# Archer.net
KiCad netlist of a schematic drawn in EAGLE
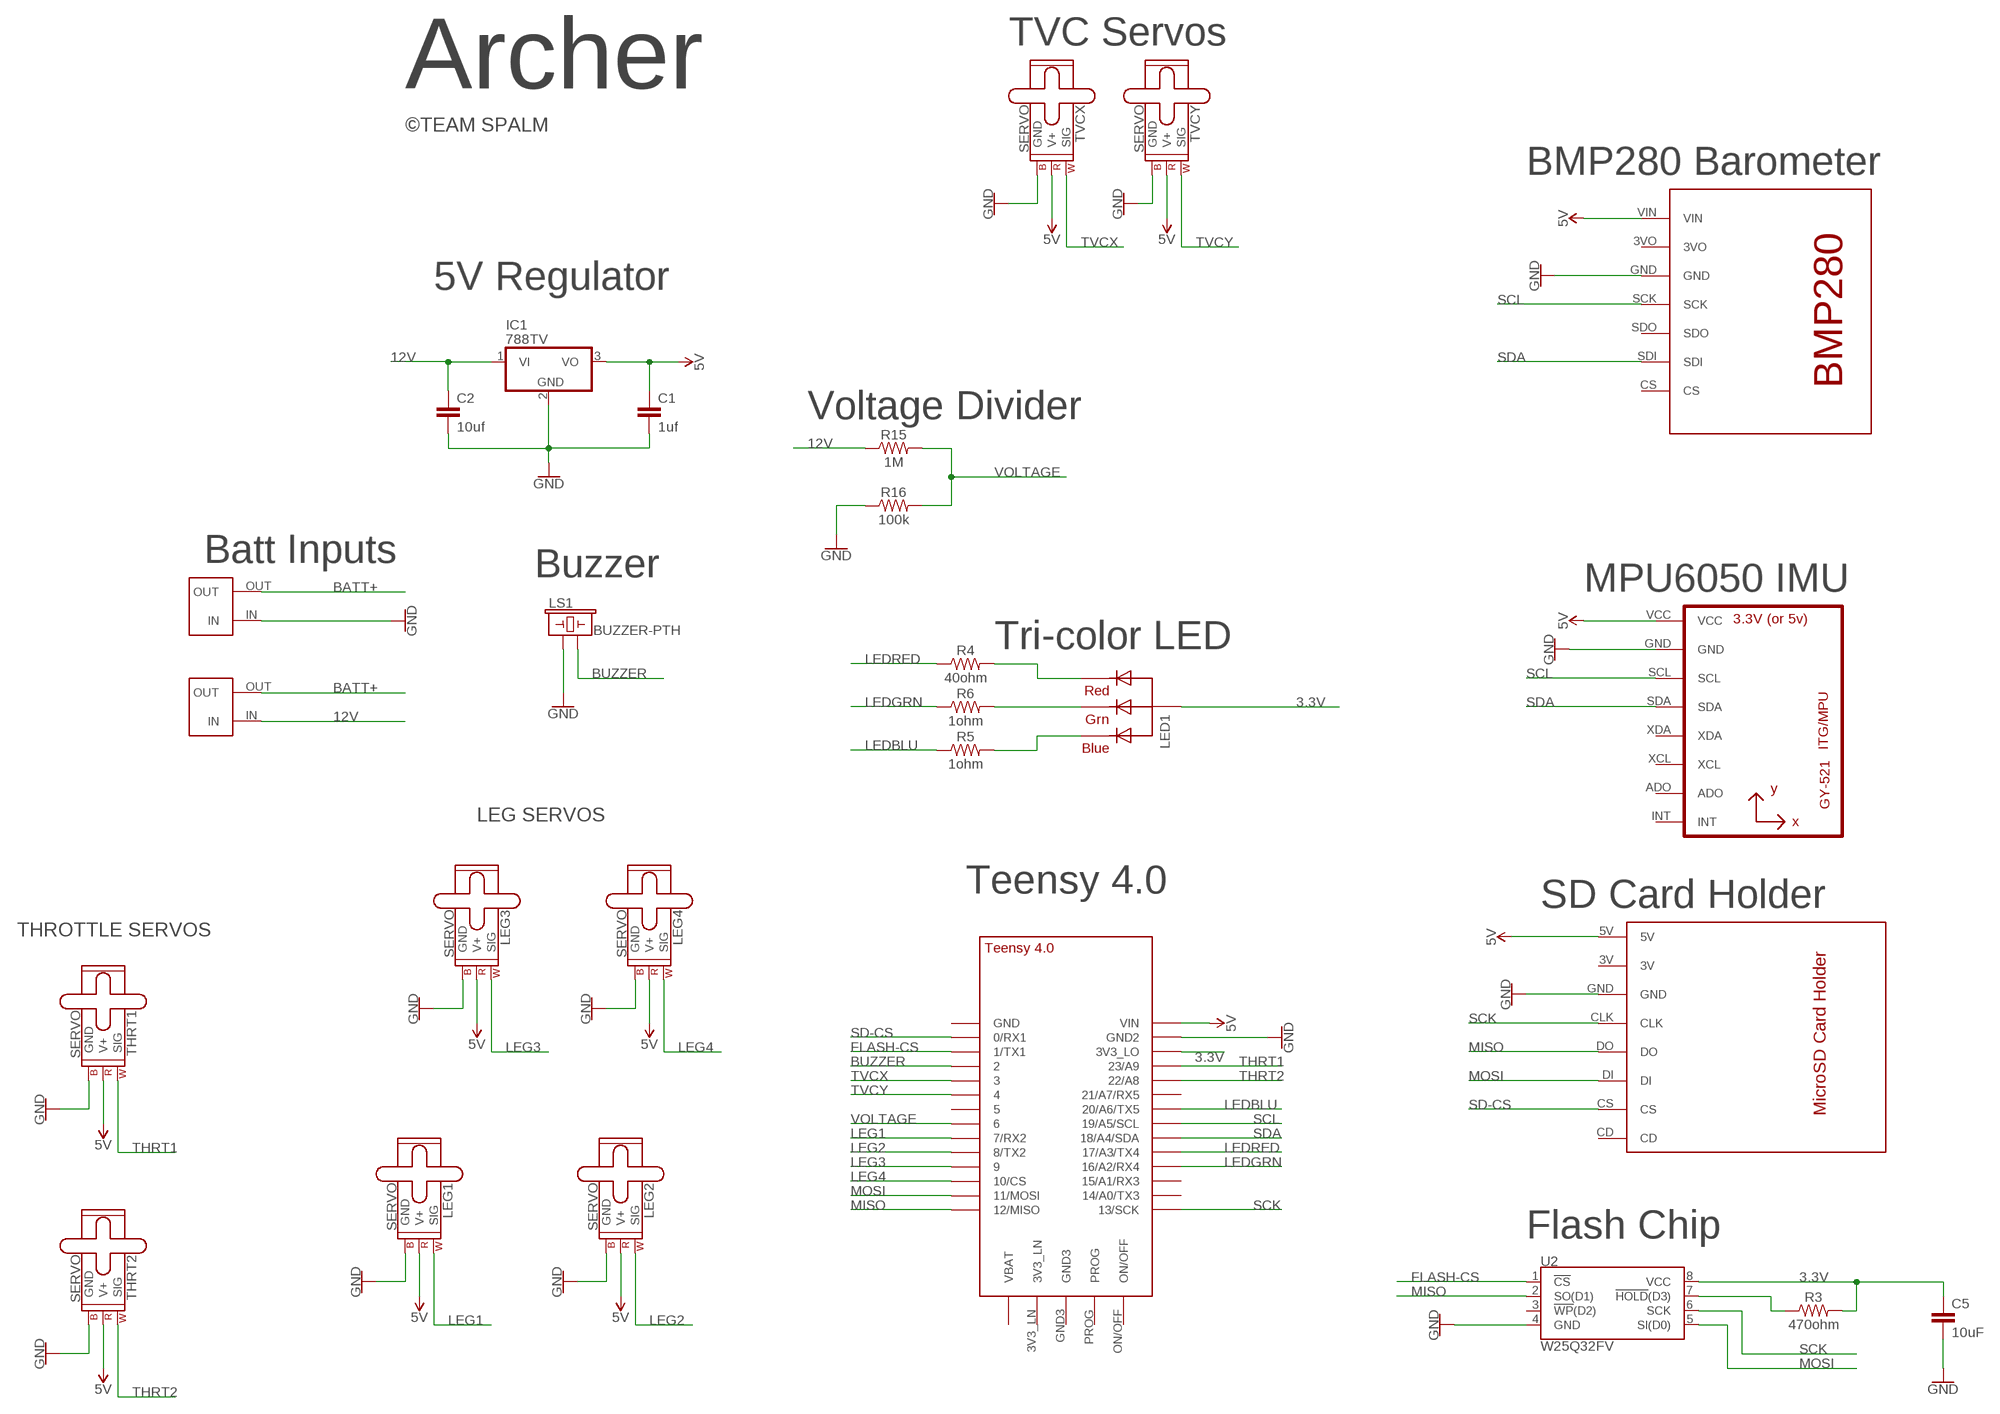
[diagram p0: schematic, sheet 1]

(export (version "E")
  (design (tool "Eeschema 10.0.6"))
  (components
    (comp (ref "C1")
      (value "1uf")
      (footprint "eagle-import:CAP-PTH-2.54")
      (libsource (lib "eagle-import") (part "22PF-PTH-2.54MM-200V-5%"))
    )
    (comp (ref "C2")
      (value "10uf")
      (footprint "eagle-import:CAP-PTH-2.54")
      (libsource (lib "eagle-import") (part "22PF-PTH-2.54MM-200V-5%"))
    )
    (comp (ref "C5")
      (value "10uF")
      (footprint "eagle-import:CAP-PTH-2.54")
      (libsource (lib "eagle-import") (part "22PF-PTH-2.54MM-200V-5%"))
    )
    (comp (ref "IC1")
      (value "788TV")
      (footprint "eagle-import:TO220V")
      (libsource (lib "eagle-import") (part "78TV8"))
    )
    (comp (ref "LED1")
      (value "RGBLED_CA-5MM")
      (footprint "eagle-import:LED5MMRGB")
      (libsource (lib "eagle-import") (part "RGBLED_CA-5MM"))
    )
    (comp (ref "LEG1")
      (value "SERVO")
      (footprint "eagle-import:1X03")
      (libsource (lib "eagle-import") (part "SERVO"))
    )
    (comp (ref "LEG2")
      (value "SERVO")
      (footprint "eagle-import:1X03")
      (libsource (lib "eagle-import") (part "SERVO"))
    )
    (comp (ref "LEG3")
      (value "SERVO")
      (footprint "eagle-import:1X03")
      (libsource (lib "eagle-import") (part "SERVO"))
    )
    (comp (ref "LEG4")
      (value "SERVO")
      (footprint "eagle-import:1X03")
      (libsource (lib "eagle-import") (part "SERVO"))
    )
    (comp (ref "LS1")
      (value "BUZZER-PTH")
      (footprint "eagle-import:BUZZER-12MM")
      (libsource (lib "eagle-import") (part "BUZZER-PTH"))
    )
    (comp (ref "R3")
      (value "470ohm")
      (footprint "eagle-import:AXIAL-0.3")
      (libsource (lib "eagle-import") (part "10MOHM-HORIZ-1/4W-5%"))
    )
    (comp (ref "R4")
      (value "40ohm")
      (footprint "eagle-import:AXIAL-0.3")
      (libsource (lib "eagle-import") (part "10MOHM-HORIZ-1/4W-5%"))
    )
    (comp (ref "R5")
      (value "1ohm")
      (footprint "eagle-import:AXIAL-0.3")
      (libsource (lib "eagle-import") (part "10MOHM-HORIZ-1/4W-5%"))
    )
    (comp (ref "R6")
      (value "1ohm")
      (footprint "eagle-import:AXIAL-0.3")
      (libsource (lib "eagle-import") (part "10MOHM-HORIZ-1/4W-5%"))
    )
    (comp (ref "R15")
      (value "1M")
      (footprint "eagle-import:AXIAL-0.3")
      (libsource (lib "eagle-import") (part "10MOHM-HORIZ-1/4W-5%"))
    )
    (comp (ref "R16")
      (value "100k")
      (footprint "eagle-import:AXIAL-0.3")
      (libsource (lib "eagle-import") (part "10MOHM-HORIZ-1/4W-5%"))
    )
    (comp (ref "TEENSY_4.0")
      (value "TEENSY_4.0")
      (footprint "eagle-import:TEENSY_4.0")
      (libsource (lib "eagle-import") (part "TEENSY_4.0"))
    )
    (comp (ref "THRT1")
      (value "SERVO")
      (footprint "eagle-import:1X03")
      (libsource (lib "eagle-import") (part "SERVO"))
    )
    (comp (ref "THRT2")
      (value "SERVO")
      (footprint "eagle-import:1X03")
      (libsource (lib "eagle-import") (part "SERVO"))
    )
    (comp (ref "TVCX")
      (value "SERVO")
      (footprint "eagle-import:1X03")
      (libsource (lib "eagle-import") (part "SERVO"))
    )
    (comp (ref "TVCY")
      (value "SERVO")
      (footprint "eagle-import:1X03")
      (libsource (lib "eagle-import") (part "SERVO"))
    )
    (comp (ref "U$2")
      (value "BMP280")
      (footprint "eagle-import:BMP280")
      (libsource (lib "eagle-import") (part "BMP280"))
    )
    (comp (ref "U$3")
      (value "MICROSDCARDHOLDER")
      (footprint "eagle-import:SDCARDHOLDER")
      (libsource (lib "eagle-import") (part "MICROSDCARDHOLDER"))
    )
    (comp (ref "U$8")
      (value "BLACKTERMBLOCK")
      (footprint "eagle-import:BLACKTERMBLOCK")
      (libsource (lib "eagle-import") (part "BLACKTERMBLOCK"))
    )
    (comp (ref "U$9")
      (value "BLACKTERMBLOCK")
      (footprint "eagle-import:BLACKTERMBLOCK")
      (libsource (lib "eagle-import") (part "BLACKTERMBLOCK"))
    )
    (comp (ref "U1")
      (value "GY-521MPU6050")
      (footprint "eagle-import:GY-521")
      (libsource (lib "eagle-import") (part "GY-521MPU6050"))
    )
    (comp (ref "U2")
      (value "W25Q32FV")
      (footprint "eagle-import:SOIC-8")
      (libsource (lib "eagle-import") (part "W25Q32FVSS"))
    )
  )
  (nets
    (net (code "1") (name "/3.3V") (class "Default")
      (node (ref "C5") (pin "1") (pinfunction "1_1") (pintype "passive"))
      (node (ref "LED1") (pin "2") (pinfunction "VCC_2") (pintype "bidirectional"))
      (node (ref "R3") (pin "P$2") (pinfunction "2_P$2") (pintype "passive"))
      (node (ref "TEENSY_4.0") (pin "3V3_LO") (pinfunction "3V3_LO_3V3_LO") (pintype "bidirectional"))
      (node (ref "U2") (pin "8") (pinfunction "VCC_8") (pintype "bidirectional"))
    )
    (net (code "2") (name "/12V") (class "Default")
      (node (ref "C2") (pin "1") (pinfunction "1_1") (pintype "passive"))
      (node (ref "IC1") (pin "1") (pinfunction "VI_1") (pintype "input"))
      (node (ref "R15") (pin "P$1") (pinfunction "1_P$1") (pintype "passive"))
      (node (ref "U$9") (pin "IN") (pinfunction "IN_IN") (pintype "bidirectional"))
    )
    (net (code "3") (name "/BATT+") (class "Default")
      (node (ref "U$8") (pin "OUT") (pinfunction "OUT_OUT") (pintype "bidirectional"))
      (node (ref "U$9") (pin "OUT") (pinfunction "OUT_OUT") (pintype "bidirectional"))
    )
    (net (code "4") (name "/BUZZER") (class "Default")
      (node (ref "LS1") (pin "-") (pinfunction "2_-") (pintype "passive"))
      (node (ref "TEENSY_4.0") (pin "2") (pinfunction "2_2") (pintype "bidirectional"))
    )
    (net (code "5") (name "/FLASH-CS") (class "Default")
      (node (ref "TEENSY_4.0") (pin "1/TX") (pinfunction "1/TX1_1/TX") (pintype "bidirectional"))
      (node (ref "U2") (pin "1") (pinfunction "~{CS}_1") (pintype "bidirectional"))
    )
    (net (code "6") (name "/LEDBLU") (class "Default")
      (node (ref "R5") (pin "P$1") (pinfunction "1_P$1") (pintype "passive"))
      (node (ref "TEENSY_4.0") (pin "20/A6") (pinfunction "20/A6/TX5_20/A6") (pintype "bidirectional"))
    )
    (net (code "7") (name "/LEDGRN") (class "Default")
      (node (ref "R6") (pin "P$1") (pinfunction "1_P$1") (pintype "passive"))
      (node (ref "TEENSY_4.0") (pin "16/A2") (pinfunction "16/A2/RX4_16/A2") (pintype "bidirectional"))
    )
    (net (code "8") (name "/LEDRED") (class "Default")
      (node (ref "R4") (pin "P$1") (pinfunction "1_P$1") (pintype "passive"))
      (node (ref "TEENSY_4.0") (pin "17/A3") (pinfunction "17/A3/TX4_17/A3") (pintype "bidirectional"))
    )
    (net (code "9") (name "/LEG1") (class "Default")
      (node (ref "LEG1") (pin "1") (pinfunction "SIG_1") (pintype "bidirectional"))
      (node (ref "TEENSY_4.0") (pin "7") (pinfunction "7/RX2_7") (pintype "bidirectional"))
    )
    (net (code "10") (name "/LEG2") (class "Default")
      (node (ref "LEG2") (pin "1") (pinfunction "SIG_1") (pintype "bidirectional"))
      (node (ref "TEENSY_4.0") (pin "8") (pinfunction "8/TX2_8") (pintype "bidirectional"))
    )
    (net (code "11") (name "/LEG3") (class "Default")
      (node (ref "LEG3") (pin "1") (pinfunction "SIG_1") (pintype "bidirectional"))
      (node (ref "TEENSY_4.0") (pin "9/CS") (pinfunction "9_9/CS") (pintype "bidirectional"))
    )
    (net (code "12") (name "/LEG4") (class "Default")
      (node (ref "LEG4") (pin "1") (pinfunction "SIG_1") (pintype "bidirectional"))
      (node (ref "TEENSY_4.0") (pin "10/CS") (pinfunction "10/CS_10/CS") (pintype "bidirectional"))
    )
    (net (code "13") (name "/MISO") (class "Default")
      (node (ref "TEENSY_4.0") (pin "12/MISO") (pinfunction "12/MISO_12/MISO") (pintype "bidirectional"))
      (node (ref "U$3") (pin "DO") (pinfunction "DO_DO") (pintype "bidirectional"))
      (node (ref "U2") (pin "2") (pinfunction "SO(D1)_2") (pintype "bidirectional"))
    )
    (net (code "14") (name "/MOSI") (class "Default")
      (node (ref "TEENSY_4.0") (pin "11/MOSI") (pinfunction "11/MOSI_11/MOSI") (pintype "bidirectional"))
      (node (ref "U$3") (pin "DI") (pinfunction "DI_DI") (pintype "bidirectional"))
      (node (ref "U2") (pin "5") (pinfunction "SI(D0)_5") (pintype "bidirectional"))
    )
    (net (code "15") (name "/SCK") (class "Default")
      (node (ref "TEENSY_4.0") (pin "13/SCK") (pinfunction "13/SCK_13/SCK") (pintype "bidirectional"))
      (node (ref "U$3") (pin "CLK") (pinfunction "CLK_CLK") (pintype "bidirectional"))
      (node (ref "U2") (pin "6") (pinfunction "SCK_6") (pintype "bidirectional"))
    )
    (net (code "16") (name "/SCL") (class "Default")
      (node (ref "TEENSY_4.0") (pin "19/A5/SCL") (pinfunction "19/A5/SCL_19/A5/SCL") (pintype "bidirectional"))
      (node (ref "U$2") (pin "SCK") (pinfunction "SCK_SCK") (pintype "bidirectional"))
      (node (ref "U1") (pin "SCL") (pinfunction "SCL_SCL") (pintype "bidirectional"))
    )
    (net (code "17") (name "/SD-CS") (class "Default")
      (node (ref "TEENSY_4.0") (pin "0/RX") (pinfunction "0/RX1_0/RX") (pintype "bidirectional"))
      (node (ref "U$3") (pin "CS") (pinfunction "CS_CS") (pintype "bidirectional"))
    )
    (net (code "18") (name "/SDA") (class "Default")
      (node (ref "TEENSY_4.0") (pin "18/A4/SDA") (pinfunction "18/A4/SDA_18/A4/SDA") (pintype "bidirectional"))
      (node (ref "U$2") (pin "SDI") (pinfunction "SDI_SDI") (pintype "bidirectional"))
      (node (ref "U1") (pin "SDA") (pinfunction "SDA_SDA") (pintype "bidirectional"))
    )
    (net (code "19") (name "/THRT1") (class "Default")
      (node (ref "TEENSY_4.0") (pin "23/A9") (pinfunction "23/A9_23/A9") (pintype "bidirectional"))
      (node (ref "THRT1") (pin "1") (pinfunction "SIG_1") (pintype "bidirectional"))
    )
    (net (code "20") (name "/THRT2") (class "Default")
      (node (ref "TEENSY_4.0") (pin "22/A8") (pinfunction "22/A8_22/A8") (pintype "bidirectional"))
      (node (ref "THRT2") (pin "1") (pinfunction "SIG_1") (pintype "bidirectional"))
    )
    (net (code "21") (name "/TVCX") (class "Default")
      (node (ref "TEENSY_4.0") (pin "3/CANTX") (pinfunction "3_3/CANTX") (pintype "bidirectional"))
      (node (ref "TVCX") (pin "1") (pinfunction "SIG_1") (pintype "bidirectional"))
    )
    (net (code "22") (name "/TVCY") (class "Default")
      (node (ref "TEENSY_4.0") (pin "4/CANRX") (pinfunction "4_4/CANRX") (pintype "bidirectional"))
      (node (ref "TVCY") (pin "1") (pinfunction "SIG_1") (pintype "bidirectional"))
    )
    (net (code "23") (name "/VOLTAGE") (class "Default")
      (node (ref "R15") (pin "P$2") (pinfunction "2_P$2") (pintype "passive"))
      (node (ref "R16") (pin "P$2") (pinfunction "2_P$2") (pintype "passive"))
      (node (ref "TEENSY_4.0") (pin "6") (pinfunction "6_6") (pintype "bidirectional"))
    )
    (net (code "24") (name "5V") (class "Default")
      (node (ref "C1") (pin "1") (pinfunction "1_1") (pintype "passive"))
      (node (ref "IC1") (pin "3") (pinfunction "VO_3") (pintype "passive"))
      (node (ref "LEG1") (pin "2") (pinfunction "V+_2") (pintype "bidirectional"))
      (node (ref "LEG2") (pin "2") (pinfunction "V+_2") (pintype "bidirectional"))
      (node (ref "LEG3") (pin "2") (pinfunction "V+_2") (pintype "bidirectional"))
      (node (ref "LEG4") (pin "2") (pinfunction "V+_2") (pintype "bidirectional"))
      (node (ref "TEENSY_4.0") (pin "VIN") (pinfunction "VIN_VIN") (pintype "bidirectional"))
      (node (ref "THRT1") (pin "2") (pinfunction "V+_2") (pintype "bidirectional"))
      (node (ref "THRT2") (pin "2") (pinfunction "V+_2") (pintype "bidirectional"))
      (node (ref "TVCX") (pin "2") (pinfunction "V+_2") (pintype "bidirectional"))
      (node (ref "TVCY") (pin "2") (pinfunction "V+_2") (pintype "bidirectional"))
      (node (ref "U$2") (pin "VIN") (pinfunction "VIN_VIN") (pintype "bidirectional"))
      (node (ref "U$3") (pin "5V") (pinfunction "5V_5V") (pintype "bidirectional"))
      (node (ref "U1") (pin "VCC") (pinfunction "VCC_VCC") (pintype "bidirectional"))
    )
    (net (code "25") (name "GND") (class "Default")
      (node (ref "C1") (pin "2") (pinfunction "2_2") (pintype "passive"))
      (node (ref "C2") (pin "2") (pinfunction "2_2") (pintype "passive"))
      (node (ref "C5") (pin "2") (pinfunction "2_2") (pintype "passive"))
      (node (ref "IC1") (pin "2") (pinfunction "GND_2") (pintype "passive"))
      (node (ref "LEG1") (pin "3") (pinfunction "GND_3") (pintype "bidirectional"))
      (node (ref "LEG2") (pin "3") (pinfunction "GND_3") (pintype "bidirectional"))
      (node (ref "LEG3") (pin "3") (pinfunction "GND_3") (pintype "bidirectional"))
      (node (ref "LEG4") (pin "3") (pinfunction "GND_3") (pintype "bidirectional"))
      (node (ref "LS1") (pin "+") (pinfunction "1_+") (pintype "passive"))
      (node (ref "R16") (pin "P$1") (pinfunction "1_P$1") (pintype "passive"))
      (node (ref "TEENSY_4.0") (pin "GND2") (pinfunction "GND2_GND2") (pintype "bidirectional"))
      (node (ref "THRT1") (pin "3") (pinfunction "GND_3") (pintype "bidirectional"))
      (node (ref "THRT2") (pin "3") (pinfunction "GND_3") (pintype "bidirectional"))
      (node (ref "TVCX") (pin "3") (pinfunction "GND_3") (pintype "bidirectional"))
      (node (ref "TVCY") (pin "3") (pinfunction "GND_3") (pintype "bidirectional"))
      (node (ref "U$2") (pin "GND") (pinfunction "GND_GND") (pintype "bidirectional"))
      (node (ref "U$3") (pin "GND") (pinfunction "GND_GND") (pintype "bidirectional"))
      (node (ref "U$8") (pin "IN") (pinfunction "IN_IN") (pintype "bidirectional"))
      (node (ref "U1") (pin "GND") (pinfunction "GND_GND") (pintype "bidirectional"))
      (node (ref "U2") (pin "4") (pinfunction "GND_4") (pintype "bidirectional"))
    )
    (net (code "26") (name "Net-(LED1-BLUE)") (class "Default")
      (node (ref "LED1") (pin "4") (pinfunction "BLUE_4") (pintype "bidirectional"))
      (node (ref "R5") (pin "P$2") (pinfunction "2_P$2") (pintype "passive"))
    )
    (net (code "27") (name "Net-(LED1-GREEN)") (class "Default")
      (node (ref "LED1") (pin "3") (pinfunction "GREEN_3") (pintype "bidirectional"))
      (node (ref "R6") (pin "P$2") (pinfunction "2_P$2") (pintype "passive"))
    )
    (net (code "28") (name "Net-(LED1-RED)") (class "Default")
      (node (ref "LED1") (pin "1") (pinfunction "RED_1") (pintype "bidirectional"))
      (node (ref "R4") (pin "P$2") (pinfunction "2_P$2") (pintype "passive"))
    )
    (net (code "29") (name "Net-(R3-1)") (class "Default")
      (node (ref "R3") (pin "P$1") (pinfunction "1_P$1") (pintype "passive"))
      (node (ref "U2") (pin "7") (pinfunction "~{HOLD}(D3)_7") (pintype "bidirectional"))
    )
    (net (code "30") (name "unconnected-(TEENSY_4.0-14{slash}A0{slash}TX3-Pad14{slash}A0)") (class "Default")
      (node (ref "TEENSY_4.0") (pin "14/A0") (pinfunction "14/A0/TX3_14/A0") (pintype "bidirectional"))
    )
    (net (code "31") (name "unconnected-(TEENSY_4.0-15{slash}A1{slash}RX3-Pad15{slash}A1)") (class "Default")
      (node (ref "TEENSY_4.0") (pin "15/A1") (pinfunction "15/A1/RX3_15/A1") (pintype "bidirectional"))
    )
    (net (code "32") (name "unconnected-(TEENSY_4.0-21{slash}A7{slash}RX5-Pad21{slash}A7)") (class "Default")
      (node (ref "TEENSY_4.0") (pin "21/A7") (pinfunction "21/A7/RX5_21/A7") (pintype "bidirectional"))
    )
    (net (code "33") (name "unconnected-(TEENSY_4.0-Pad3V3_LN)") (class "Default")
      (node (ref "TEENSY_4.0") (pin "3V3_LN") (pinfunction "3V3_LN_3V3_LN") (pintype "bidirectional"))
    )
    (net (code "34") (name "unconnected-(TEENSY_4.0-Pad5)") (class "Default")
      (node (ref "TEENSY_4.0") (pin "5") (pinfunction "5_5") (pintype "bidirectional"))
    )
    (net (code "35") (name "unconnected-(TEENSY_4.0-PadGND)") (class "Default")
      (node (ref "TEENSY_4.0") (pin "GND") (pinfunction "GND_GND") (pintype "bidirectional"))
    )
    (net (code "36") (name "unconnected-(TEENSY_4.0-PadGND3)") (class "Default")
      (node (ref "TEENSY_4.0") (pin "GND3") (pinfunction "GND3_GND3") (pintype "bidirectional"))
    )
    (net (code "37") (name "unconnected-(TEENSY_4.0-PadON{slash}OFF)") (class "Default")
      (node (ref "TEENSY_4.0") (pin "ON/OFF") (pinfunction "ON/OFF_ON/OFF") (pintype "bidirectional"))
    )
    (net (code "38") (name "unconnected-(TEENSY_4.0-PadPROG)") (class "Default")
      (node (ref "TEENSY_4.0") (pin "PROG") (pinfunction "PROG_PROG") (pintype "bidirectional"))
    )
    (net (code "39") (name "unconnected-(TEENSY_4.0-VBAT-PadVBAT\\)") (class "Default")
      (node (ref "TEENSY_4.0") (pin "VBAT\\") (pinfunction "VBAT_VBAT\\") (pintype "bidirectional"))
    )
    (net (code "40") (name "unconnected-(U$2-Pad3VO)") (class "Default")
      (node (ref "U$2") (pin "3VO") (pinfunction "3VO_3VO") (pintype "bidirectional"))
    )
    (net (code "41") (name "unconnected-(U$2-PadCS)") (class "Default")
      (node (ref "U$2") (pin "CS") (pinfunction "CS_CS") (pintype "bidirectional"))
    )
    (net (code "42") (name "unconnected-(U$2-PadSDO)") (class "Default")
      (node (ref "U$2") (pin "SDO") (pinfunction "SDO_SDO") (pintype "bidirectional"))
    )
    (net (code "43") (name "unconnected-(U$3-Pad3V)") (class "Default")
      (node (ref "U$3") (pin "3V") (pinfunction "3V_3V") (pintype "bidirectional"))
    )
    (net (code "44") (name "unconnected-(U$3-PadCD)") (class "Default")
      (node (ref "U$3") (pin "CD") (pinfunction "CD_CD") (pintype "bidirectional"))
    )
    (net (code "45") (name "unconnected-(U1-PadADO)") (class "Default")
      (node (ref "U1") (pin "ADO") (pinfunction "ADO_ADO") (pintype "bidirectional"))
    )
    (net (code "46") (name "unconnected-(U1-PadINT)") (class "Default")
      (node (ref "U1") (pin "INT") (pinfunction "INT_INT") (pintype "bidirectional"))
    )
    (net (code "47") (name "unconnected-(U1-PadXCL)") (class "Default")
      (node (ref "U1") (pin "XCL") (pinfunction "XCL_XCL") (pintype "bidirectional"))
    )
    (net (code "48") (name "unconnected-(U1-PadXDA)") (class "Default")
      (node (ref "U1") (pin "XDA") (pinfunction "XDA_XDA") (pintype "bidirectional"))
    )
    (net (code "49") (name "unconnected-(U2-~{WP}(D2)-Pad3)") (class "Default")
      (node (ref "U2") (pin "3") (pinfunction "~{WP}(D2)_3") (pintype "bidirectional"))
    )
  )
)
